# Pag2_Battery_Charger.net
KiCad netlist of a schematic drawn in Altium Designer
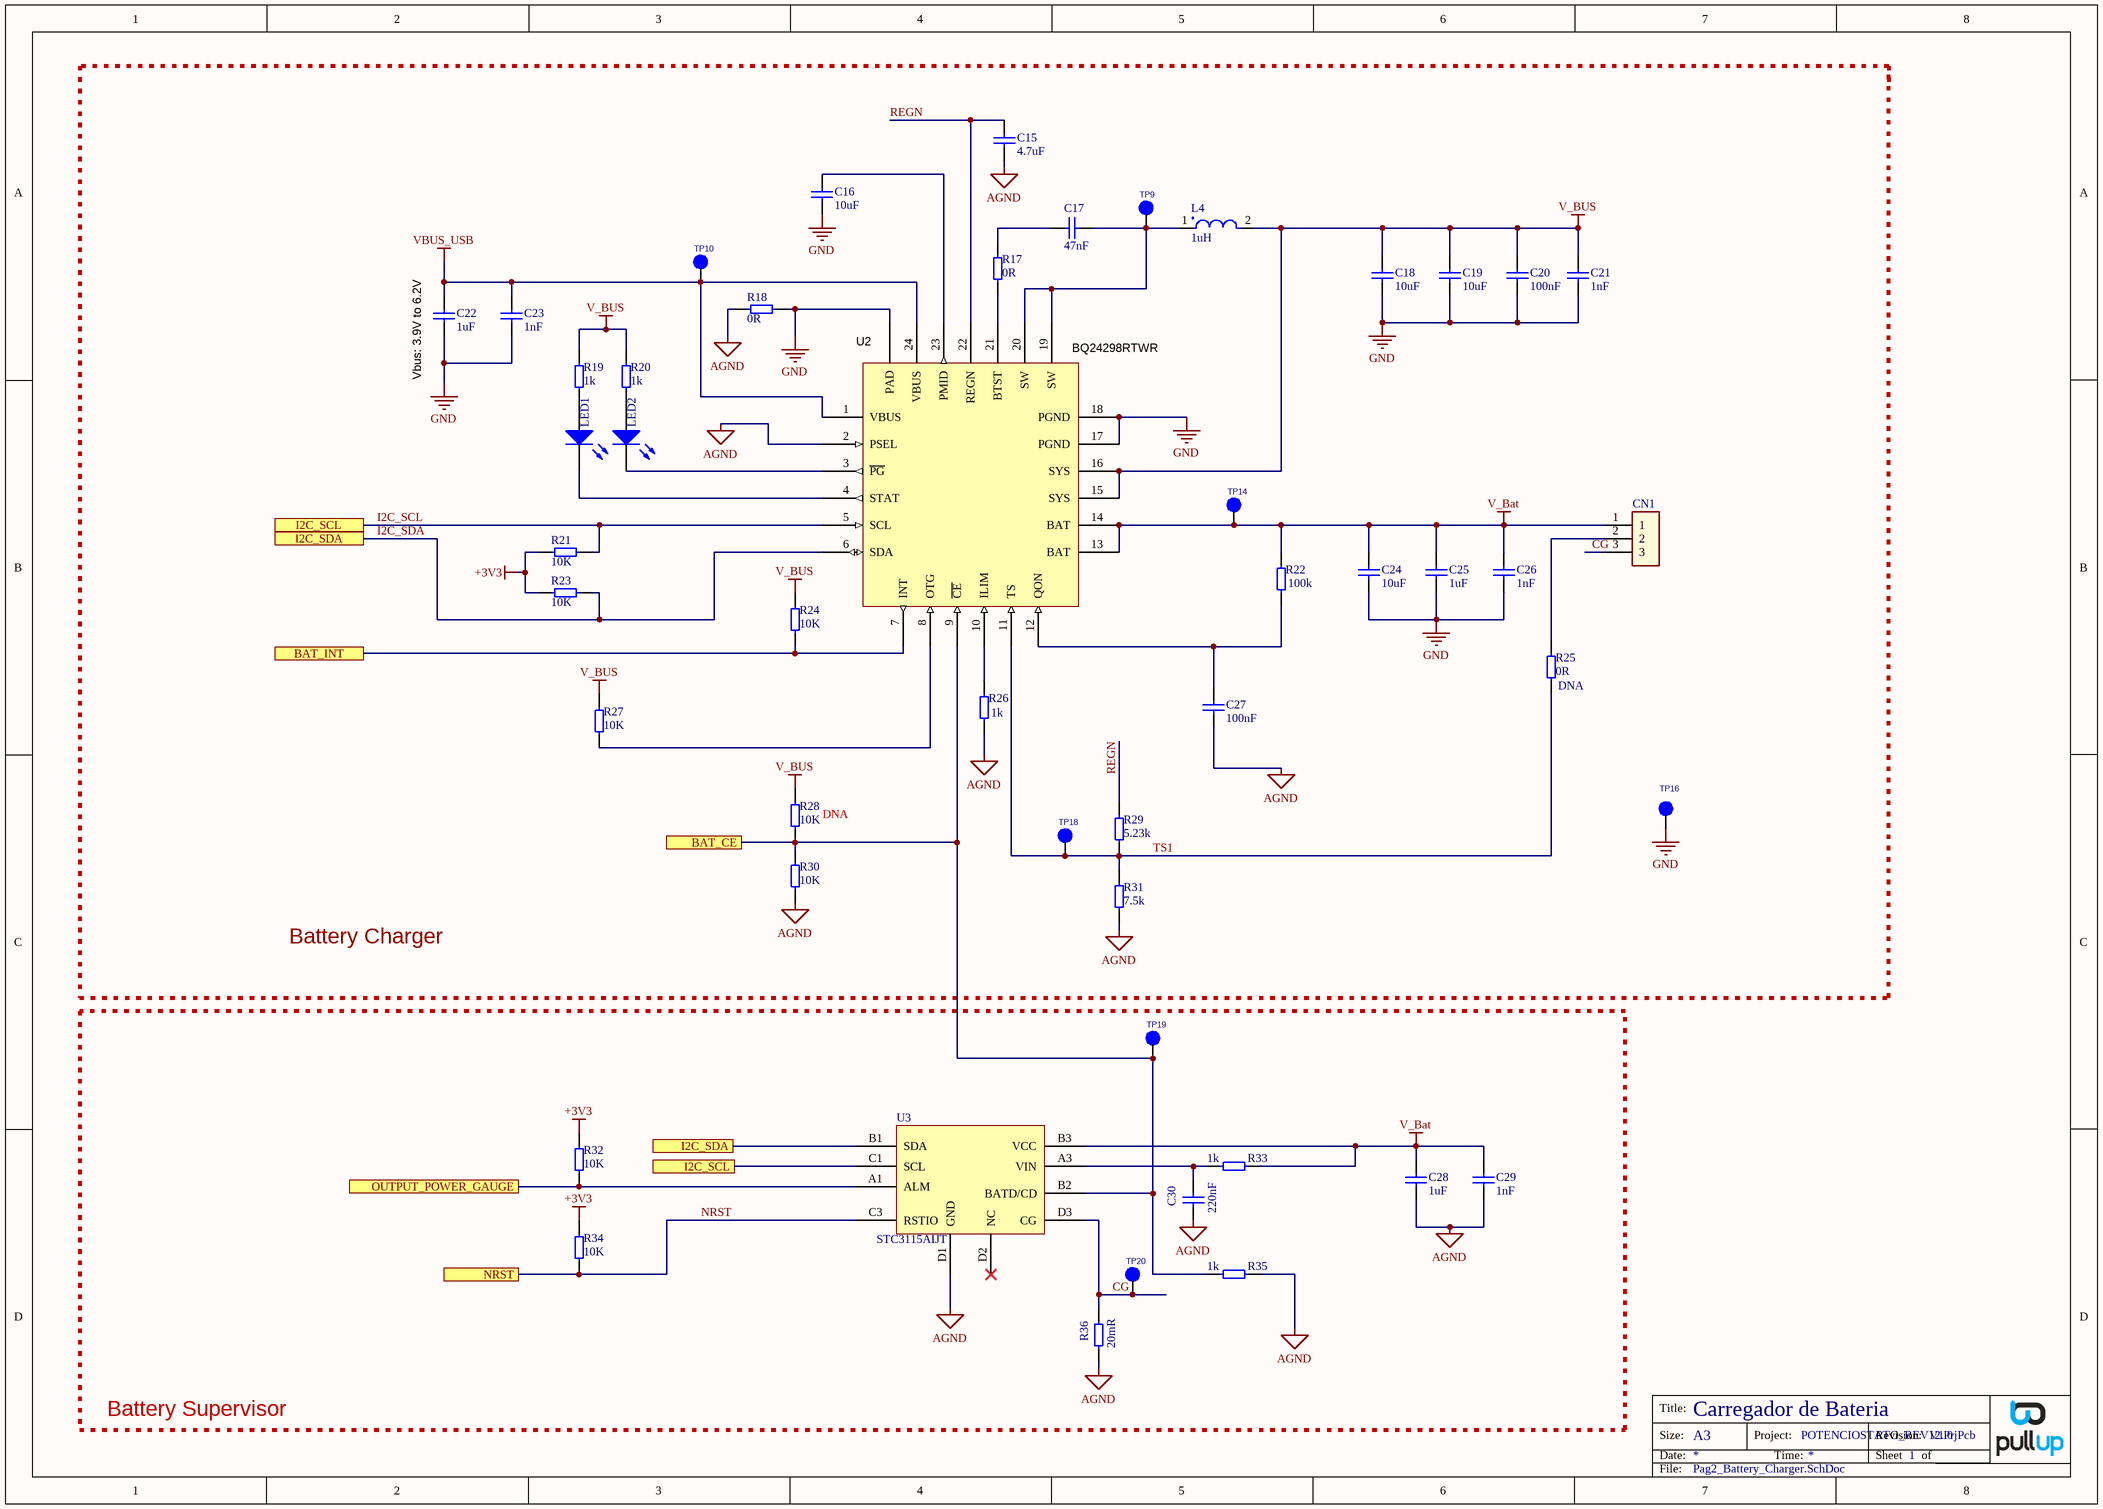
[diagram p0: Pag2_Battery_Charger.SchDoc]

(export (version "E")
  (design (tool "Eeschema 10.0.6"))
  (components
    (comp (ref "C15")
      (value "4.7uF")
      (footprint "0603")
      (description "Multilayer Ceramic Capacitors MLCC - SMD/SMT 4.7uF 6.3V 0603 10%")
      (fields (field (name "MANUFACTURER") "Taiyo Yuden") (field (name "MPN") "JMK105BBJ475MV-F"))
      (libsource (lib "Database_Pullup") (part "Cap"))
    )
    (comp (ref "C16")
      (value "10uF")
      (footprint "0603")
      (description "Multilayer Ceramic Capacitors MLCC - SMD/SMT 10uF 0603 10V 10%")
      (fields (field (name "MANUFACTURER") "Murata Electronics") (field (name "MPN") "GRM188R61A106KE69D"))
      (libsource (lib "Database_Pullup") (part "Cap"))
    )
    (comp (ref "C17")
      (value "47nF")
      (footprint "0603")
      (description "Multilayer Ceramic Capacitors MLCC - SMD/SMT 47nF 0603 16V 10%")
      (fields (field (name "MANUFACTURER") "AVX") (field (name "MPN") "0603YC473KAT2A"))
      (libsource (lib "Database_Pullup") (part "Cap"))
    )
    (comp (ref "C18")
      (value "10uF")
      (footprint "0603")
      (description "Multilayer Ceramic Capacitors MLCC - SMD/SMT 10uF 0603 10V 10%")
      (fields (field (name "MANUFACTURER") "Murata Electronics") (field (name "MPN") "GRM188R61A106KE69D"))
      (libsource (lib "Database_Pullup") (part "Cap"))
    )
    (comp (ref "C19")
      (value "10uF")
      (footprint "0603")
      (description "Multilayer Ceramic Capacitors MLCC - SMD/SMT 10uF 0603 10V 10%")
      (fields (field (name "MANUFACTURER") "Murata Electronics") (field (name "MPN") "GRM188R61A106KE69D"))
      (libsource (lib "Database_Pullup") (part "Cap"))
    )
    (comp (ref "C20")
      (value "100nF")
      (footprint "0603")
      (description "Multilayer Ceramic Capacitors MLCC - SMD/SMT 100nF 16V 0603 10%")
      (fields (field (name "MANUFACTURER") "KEMET") (field (name "MPN") "C0603C104K4RACTU"))
      (libsource (lib "Database_Pullup") (part "Cap"))
    )
    (comp (ref "C21")
      (value "1nF")
      (footprint "0603")
      (description "Multilayer Ceramic Capacitors MLCC - SMD/SMT 25V 1nF 0603 25V 5%")
      (fields (field (name "MANUFACTURER") "Yageo") (field (name "MPN") "CC0603JRX7R8BB102"))
      (libsource (lib "Database_Pullup") (part "Cap"))
    )
    (comp (ref "C22")
      (value "1uF")
      (footprint "0603")
      (description "Multilayer Ceramic Capacitors MLCC - SMD/SMT 1uF 25V 0603 10%")
      (fields
        (field (name "MANUFACTURER") "Samsung Electro-Mechanics")
        (field (name "MPN") "CL10A105KA8NNNC")
      )
      (libsource (lib "Database_Pullup") (part "Cap"))
    )
    (comp (ref "C23")
      (value "1nF")
      (footprint "0603")
      (description "Multilayer Ceramic Capacitors MLCC - SMD/SMT 25V 1nF 0603 25V 5%")
      (fields (field (name "MANUFACTURER") "Yageo") (field (name "MPN") "CC0603JRX7R8BB102"))
      (libsource (lib "Database_Pullup") (part "Cap"))
    )
    (comp (ref "C24")
      (value "10uF")
      (footprint "0603")
      (description "Multilayer Ceramic Capacitors MLCC - SMD/SMT 10uF 0603 10V 10%")
      (fields (field (name "MANUFACTURER") "Murata Electronics") (field (name "MPN") "GRM188R61A106KE69D"))
      (libsource (lib "Database_Pullup") (part "Cap"))
    )
    (comp (ref "C25")
      (value "1uF")
      (footprint "0603")
      (description "Multilayer Ceramic Capacitors MLCC - SMD/SMT 1uF 25V 0603 10%")
      (fields
        (field (name "MANUFACTURER") "Samsung Electro-Mechanics")
        (field (name "MPN") "CL10A105KA8NNNC")
      )
      (libsource (lib "Database_Pullup") (part "Cap"))
    )
    (comp (ref "C26")
      (value "1nF")
      (footprint "0603")
      (description "Multilayer Ceramic Capacitors MLCC - SMD/SMT 25V 1nF 0603 25V 5%")
      (fields (field (name "MANUFACTURER") "Yageo") (field (name "MPN") "CC0603JRX7R8BB102"))
      (libsource (lib "Database_Pullup") (part "Cap"))
    )
    (comp (ref "C27")
      (value "100nF")
      (footprint "0603")
      (description "Multilayer Ceramic Capacitors MLCC - SMD/SMT 100nF 16V 0603 10%")
      (fields (field (name "MANUFACTURER") "KEMET") (field (name "MPN") "C0603C104K4RACTU"))
      (libsource (lib "Database_Pullup") (part "Cap"))
    )
    (comp (ref "C28")
      (value "1uF")
      (footprint "0603")
      (description "Multilayer Ceramic Capacitors MLCC - SMD/SMT 1uF 25V 0603 10%")
      (fields
        (field (name "MANUFACTURER") "Samsung Electro-Mechanics")
        (field (name "MPN") "CL10A105KA8NNNC")
      )
      (libsource (lib "Database_Pullup") (part "Cap"))
    )
    (comp (ref "C29")
      (value "1nF")
      (footprint "0603")
      (description "Multilayer Ceramic Capacitors MLCC - SMD/SMT 25V 1nF 0603 25V 5%")
      (fields (field (name "MANUFACTURER") "Yageo") (field (name "MPN") "CC0603JRX7R8BB102"))
      (libsource (lib "Database_Pullup") (part "Cap"))
    )
    (comp (ref "C30")
      (value "220nF")
      (footprint "0603")
      (description "Multilayer Ceramic Capacitors MLCC - SMD/SMT 220nF 0603 16V 10%")
      (fields (field (name "MANUFACTURER") "Yageo") (field (name "MPN") "CC0603KRX7R7BB224"))
      (libsource (lib "Database_Pullup") (part "Cap"))
    )
    (comp (ref "CN1")
      (value "~")
      (footprint "HDR1X3 Large")
      (fields (field (name "MPN") "Header"))
      (libsource (lib "LIBSCH_PULLUP") (part "53254-0370"))
    )
    (comp (ref "L4")
      (value "1uH")
      (footprint "SRP4012TA")
      (description "Power Inductors - SMD 1uH 20% SMD 4012 AEC-Q200")
      (fields (field (name "MANUFACTURER") "Bourns") (field (name "MPN") "SRP4012TA-1R0M"))
      (libsource (lib "Database_Pullup") (part "IND"))
    )
    (comp (ref "LED1")
      (value "LED Green")
      (footprint "0603 - led")
      (description "Standard LEDs - SMD Green, Water Clear 60mcd, 571nm")
      (fields (field (name "MPN") "APG1608CGKC/T") (field (name "MANUFACTURER") "Kingbright"))
      (libsource (lib "Database_Pullup") (part "LED"))
    )
    (comp (ref "LED2")
      (value "LED Green")
      (footprint "0603 - led")
      (description "Standard LEDs - SMD Green, Water Clear 60mcd, 571nm")
      (fields (field (name "MPN") "APG1608CGKC/T") (field (name "MANUFACTURER") "Kingbright"))
      (libsource (lib "Database_Pullup") (part "LED"))
    )
    (comp (ref "R17")
      (value "0R")
      (footprint "0603")
      (description "Thick Film Resistors - SMD 0 Ohms 100 mW 0603 5%")
      (fields (field (name "MPN") "RC0603JR-070RL") (field (name "MANUFACTURER") "Yageo"))
      (libsource (lib "") (part "Res_2"))
    )
    (comp (ref "R18")
      (value "0R")
      (footprint "1218")
      (description "Thick Film Resistors - SMD 1watt zero ohm 1218")
      (fields (field (name "MANUFACTURER") "Yageo") (field (name "MPN") "RCL12180000Z0EK"))
      (libsource (lib "") (part "Res_1"))
    )
    (comp (ref "R19")
      (value "1k")
      (footprint "0603")
      (description "Thick Film Resistors - SMD 1 kOhms 100 mW 0603 5%")
      (fields (field (name "MPN") "RC0603JR-071KL") (field (name "MANUFACTURER") "Yageo"))
      (libsource (lib "") (part "Res_2"))
    )
    (comp (ref "R20")
      (value "1k")
      (footprint "0603")
      (description "Thick Film Resistors - SMD 1 kOhms 100 mW 0603 5%")
      (fields (field (name "MPN") "RC0603JR-071KL") (field (name "MANUFACTURER") "Yageo"))
      (libsource (lib "") (part "Res_2"))
    )
    (comp (ref "R21")
      (value "10K")
      (footprint "0603")
      (description "Thick Film Resistors - SMD 10 kOhms 100-200 mW 0603 1%")
      (fields (field (name "MANUFACTURER") "Yageo") (field (name "MPN") "RC0603FR-1310KL"))
      (libsource (lib "Database_Pullup_New") (part "Res"))
    )
    (comp (ref "R22")
      (value "100k")
      (footprint "0603")
      (description "Thick Film Resistors - SMD 100 kOhms 0603 100mW 1%")
      (fields (field (name "MPN") "RC0603FR-07100KL") (field (name "MANUFACTURER") "Yageo"))
      (libsource (lib "Database_Pullup") (part "Res"))
    )
    (comp (ref "R23")
      (value "10K")
      (footprint "0603")
      (description "Thick Film Resistors - SMD 10 kOhms 100-200 mW 0603 1%")
      (fields (field (name "MANUFACTURER") "Yageo") (field (name "MPN") "RC0603FR-1310KL"))
      (libsource (lib "Database_Pullup_New") (part "Res"))
    )
    (comp (ref "R24")
      (value "10K")
      (footprint "0603")
      (description "Thick Film Resistors - SMD 10 kOhms 100-200 mW 0603 1%")
      (fields (field (name "MANUFACTURER") "Yageo") (field (name "MPN") "RC0603FR-1310KL"))
      (libsource (lib "") (part "Res_1"))
    )
    (comp (ref "R25")
      (value "0R")
      (footprint "0603")
      (description "Thick Film Resistors - SMD 0 Ohms 100 mW 0603 5%")
      (fields
        (field (name "MPN") "RC0603JR-070RL")
        (field (name "MANUFACTURER") "Yageo")
        (field (name "PCBA") "DNA")
      )
      (libsource (lib "Database_Pullup") (part "Res"))
    )
    (comp (ref "R26")
      (value "1k")
      (footprint "0603")
      (description "Thick Film Resistors - SMD 1 kOhms 100 mW 0603 5%")
      (fields (field (name "MPN") "RC0603JR-071KL") (field (name "MANUFACTURER") "Yageo"))
      (libsource (lib "") (part "Res_2"))
    )
    (comp (ref "R27")
      (value "10K")
      (footprint "0603")
      (description "Thick Film Resistors - SMD 10 kOhms 100-200 mW 0603 1%")
      (fields (field (name "MANUFACTURER") "Yageo") (field (name "MPN") "RC0603FR-1310KL"))
      (libsource (lib "") (part "Res_1"))
    )
    (comp (ref "R28")
      (value "10K")
      (footprint "0603")
      (description "Thick Film Resistors - SMD 10 kOhms 100-200 mW 0603 1%")
      (fields
        (field (name "MANUFACTURER") "Yageo")
        (field (name "MPN") "RC0603FR-1310KL")
        (field (name "PCBA") "DNA")
      )
      (libsource (lib "") (part "Res_1"))
    )
    (comp (ref "R29")
      (value "5.23k")
      (footprint "0603")
      (description "Thick Film Resistors - SMD 5.23 kOhms 100mW 0603 1%")
      (fields (field (name "MANUFACTURER") "KOA") (field (name "MPN") "RK73H1JTTD5231F"))
      (libsource (lib "") (part "Res_2"))
    )
    (comp (ref "R30")
      (value "10K")
      (footprint "0603")
      (description "Thick Film Resistors - SMD 10 kOhms 100-200 mW 0603 1%")
      (fields (field (name "MANUFACTURER") "Yageo") (field (name "MPN") "RC0603FR-1310KL"))
      (libsource (lib "") (part "Res_1"))
    )
    (comp (ref "R31")
      (value "7.5k")
      (footprint "0603")
      (description "Thick Film Resistors - SMD 7.5 kOhms 100mW 0603 0.1%")
      (fields (field (name "MANUFACTURER") "KOA Speer") (field (name "MPN") "RN73R1JTTD7501B25"))
      (libsource (lib "") (part "Res_2"))
    )
    (comp (ref "R32")
      (value "10K")
      (footprint "0603")
      (description "Thick Film Resistors - SMD 10 kOhms 100-200 mW 0603 1%")
      (fields (field (name "MANUFACTURER") "Yageo") (field (name "MPN") "RC0603FR-1310KL"))
      (libsource (lib "") (part "Res_1"))
    )
    (comp (ref "R33")
      (value "1k")
      (footprint "0603")
      (description "Thick Film Resistors - SMD 1 kOhms 100 mW 0603 5%")
      (fields (field (name "MPN") "RC0603JR-071KL") (field (name "MANUFACTURER") "Yageo"))
      (libsource (lib "Database_Pullup_New") (part "Res"))
    )
    (comp (ref "R34")
      (value "10K")
      (footprint "0603")
      (description "Thick Film Resistors - SMD 10 kOhms 100-200 mW 0603 1%")
      (fields (field (name "MANUFACTURER") "Yageo") (field (name "MPN") "RC0603FR-1310KL"))
      (libsource (lib "") (part "Res_1"))
    )
    (comp (ref "R35")
      (value "1k")
      (footprint "0603")
      (description "Thick Film Resistors - SMD 1 kOhms 100 mW 0603 5%")
      (fields (field (name "MPN") "RC0603JR-071KL") (field (name "MANUFACTURER") "Yageo"))
      (libsource (lib "Database_Pullup_New") (part "Res"))
    )
    (comp (ref "R36")
      (value "20mR")
      (footprint "0805")
      (description "Current Sense Resistors - SMD .20mOhm 1% 1/2W")
      (fields (field (name "MPN") "CFN0603-FX-R020ELF") (field (name "MANUFACTURER") "Bourns"))
      (libsource (lib "") (part "Res_1"))
    )
    (comp (ref "TP9")
      (value "Test_Point")
      (footprint "TEST")
      (fields (field (name "MANUFACTURER") "DNA"))
      (libsource (lib "Database_Pullup") (part "TestLoop"))
    )
    (comp (ref "TP10")
      (value "Test_Point")
      (footprint "TEST")
      (fields (field (name "MANUFACTURER") "DNA"))
      (libsource (lib "Database_Pullup") (part "TestLoop"))
    )
    (comp (ref "TP14")
      (value "Test_Point")
      (footprint "TEST")
      (fields (field (name "MANUFACTURER") "DNA"))
      (libsource (lib "Database_Pullup") (part "TestLoop"))
    )
    (comp (ref "TP16")
      (value "Test_Point")
      (footprint "TEST")
      (fields (field (name "MANUFACTURER") "DNA"))
      (libsource (lib "Database_Pullup") (part "TestLoop"))
    )
    (comp (ref "TP18")
      (value "Test_Point")
      (footprint "TEST")
      (fields (field (name "MANUFACTURER") "DNA"))
      (libsource (lib "Database_Pullup") (part "TestLoop"))
    )
    (comp (ref "TP19")
      (value "Test_Point")
      (footprint "TEST")
      (fields (field (name "MANUFACTURER") "DNA"))
      (libsource (lib "Database_Pullup") (part "TestLoop"))
    )
    (comp (ref "TP20")
      (value "Test_Point")
      (footprint "TEST")
      (fields (field (name "MANUFACTURER") "DNA"))
      (libsource (lib "Database_Pullup") (part "TestLoop"))
    )
    (comp (ref "U2")
      (value "BQ24298RTWR")
      (footprint "WQFN-24")
      (fields (field (name "MANUFACTURER") "Texas Instruments"))
      (libsource (lib "Database_Pullup") (part "BQ24298RTWT"))
    )
    (comp (ref "U3")
      (value "STC3115AIJT")
      (footprint "CSP1.4X2.04")
      (description "Battery Management CONDITIONING & INTERFACES")
      (fields (field (name "MANUFACTURER") "STMicroelectronics"))
      (libsource (lib "LIBSCH_PULLUP") (part "STC3100"))
    )
  )
  (nets
    (net (code "1") (name "+3V3") (class "Default")
      (node (ref "R21") (pin "2") (pinfunction "2_2") (pintype "passive"))
      (node (ref "R23") (pin "2") (pinfunction "2_2") (pintype "passive"))
      (node (ref "R32") (pin "1") (pinfunction "1_1") (pintype "passive"))
      (node (ref "R34") (pin "1") (pinfunction "1_1") (pintype "passive"))
    )
    (net (code "2") (name "/BAT_CE") (class "Default")
      (node (ref "R28") (pin "2") (pinfunction "2_2") (pintype "passive"))
      (node (ref "R30") (pin "1") (pinfunction "1_1") (pintype "passive"))
      (node (ref "R35") (pin "2") (pinfunction "2_2") (pintype "passive"))
      (node (ref "TP19") (pin "1") (pinfunction "Pin1_1") (pintype "passive"))
      (node (ref "U2") (pin "9") (pinfunction "CE_9") (pintype "input"))
      (node (ref "U3") (pin "B2") (pinfunction "BATD/CD_B2") (pintype "passive"))
    )
    (net (code "3") (name "/BAT_INT") (class "Default")
      (node (ref "R24") (pin "2") (pinfunction "2_2") (pintype "passive"))
      (node (ref "U2") (pin "7") (pinfunction "INT_7") (pintype "output"))
    )
    (net (code "4") (name "/CG") (class "Default")
      (node (ref "CN1") (pin "3") (pinfunction "3_3") (pintype "passive"))
      (node (ref "R36") (pin "1") (pinfunction "1_1") (pintype "passive"))
      (node (ref "TP20") (pin "1") (pinfunction "Pin1_1") (pintype "passive"))
      (node (ref "U3") (pin "D3") (pinfunction "CG_D3") (pintype "passive"))
    )
    (net (code "5") (name "/I2C_SCL") (class "Default")
      (node (ref "R21") (pin "1") (pinfunction "1_1") (pintype "passive"))
      (node (ref "U2") (pin "5") (pinfunction "SCL_5") (pintype "input"))
      (node (ref "U3") (pin "C1") (pinfunction "SCL_C1") (pintype "passive"))
    )
    (net (code "6") (name "/I2C_SDA") (class "Default")
      (node (ref "R23") (pin "1") (pinfunction "1_1") (pintype "passive"))
      (node (ref "U2") (pin "6") (pinfunction "SDA_6") (pintype "bidirectional"))
      (node (ref "U3") (pin "B1") (pinfunction "SDA_B1") (pintype "passive"))
    )
    (net (code "7") (name "/NRST") (class "Default")
      (node (ref "R34") (pin "2") (pinfunction "2_2") (pintype "passive"))
      (node (ref "U3") (pin "C3") (pinfunction "RSTIO_C3") (pintype "passive"))
    )
    (net (code "8") (name "/OUTPUT_POWER_GAUGE") (class "Default")
      (node (ref "R32") (pin "2") (pinfunction "2_2") (pintype "passive"))
      (node (ref "U3") (pin "A1") (pinfunction "ALM_A1") (pintype "passive"))
    )
    (net (code "9") (name "/REGN") (class "Default")
      (node (ref "C15") (pin "2") (pinfunction "2_2") (pintype "passive"))
      (node (ref "R29") (pin "2") (pinfunction "2_2") (pintype "passive"))
      (node (ref "U2") (pin "22") (pinfunction "REGN_22") (pintype "power_in"))
    )
    (net (code "10") (name "/TS1") (class "Default")
      (node (ref "R25") (pin "2") (pinfunction "2_2") (pintype "passive"))
      (node (ref "R29") (pin "1") (pinfunction "1_1") (pintype "passive"))
      (node (ref "R31") (pin "2") (pinfunction "2_2") (pintype "passive"))
      (node (ref "TP18") (pin "1") (pinfunction "Pin1_1") (pintype "passive"))
      (node (ref "U2") (pin "11") (pinfunction "TS_11") (pintype "input"))
    )
    (net (code "11") (name "AGND") (class "Default")
      (node (ref "C15") (pin "1") (pinfunction "1_1") (pintype "passive"))
      (node (ref "C27") (pin "1") (pinfunction "1_1") (pintype "passive"))
      (node (ref "C28") (pin "1") (pinfunction "1_1") (pintype "passive"))
      (node (ref "C29") (pin "1") (pinfunction "1_1") (pintype "passive"))
      (node (ref "C30") (pin "1") (pinfunction "1_1") (pintype "passive"))
      (node (ref "R18") (pin "1") (pinfunction "1_1") (pintype "passive"))
      (node (ref "R26") (pin "1") (pinfunction "1_1") (pintype "passive"))
      (node (ref "R30") (pin "2") (pinfunction "2_2") (pintype "passive"))
      (node (ref "R31") (pin "1") (pinfunction "1_1") (pintype "passive"))
      (node (ref "R35") (pin "1") (pinfunction "1_1") (pintype "passive"))
      (node (ref "R36") (pin "2") (pinfunction "2_2") (pintype "passive"))
      (node (ref "U2") (pin "2") (pinfunction "PSEL_2") (pintype "input"))
      (node (ref "U3") (pin "D1") (pinfunction "GND_D1") (pintype "passive"))
    )
    (net (code "12") (name "GND") (class "Default")
      (node (ref "C16") (pin "1") (pinfunction "1_1") (pintype "passive"))
      (node (ref "C18") (pin "1") (pinfunction "1_1") (pintype "passive"))
      (node (ref "C19") (pin "1") (pinfunction "1_1") (pintype "passive"))
      (node (ref "C20") (pin "1") (pinfunction "1_1") (pintype "passive"))
      (node (ref "C21") (pin "1") (pinfunction "1_1") (pintype "passive"))
      (node (ref "C22") (pin "1") (pinfunction "1_1") (pintype "passive"))
      (node (ref "C23") (pin "1") (pinfunction "1_1") (pintype "passive"))
      (node (ref "C24") (pin "1") (pinfunction "1_1") (pintype "passive"))
      (node (ref "C25") (pin "1") (pinfunction "1_1") (pintype "passive"))
      (node (ref "C26") (pin "1") (pinfunction "1_1") (pintype "passive"))
      (node (ref "R18") (pin "2") (pinfunction "2_2") (pintype "passive"))
      (node (ref "TP16") (pin "1") (pinfunction "Pin1_1") (pintype "passive"))
      (node (ref "U2") (pin "17") (pinfunction "PGND_17") (pintype "power_in"))
      (node (ref "U2") (pin "18") (pinfunction "PGND_18") (pintype "power_in"))
      (node (ref "U2") (pin "25") (pinfunction "PAD_25") (pintype "power_in"))
    )
    (net (code "13") (name "Net-(C17-Pad2)") (class "Default")
      (node (ref "C17") (pin "2") (pinfunction "2_2") (pintype "passive"))
      (node (ref "R17") (pin "2") (pinfunction "2_2") (pintype "passive"))
    )
    (net (code "14") (name "Net-(CN1-Pad2)") (class "Default")
      (node (ref "CN1") (pin "2") (pinfunction "2_2") (pintype "passive"))
      (node (ref "R25") (pin "1") (pinfunction "1_1") (pintype "passive"))
    )
    (net (code "15") (name "Net-(LED1-A)") (class "Default")
      (node (ref "LED1") (pin "1") (pinfunction "A_1") (pintype "passive"))
      (node (ref "R19") (pin "1") (pinfunction "1_1") (pintype "passive"))
    )
    (net (code "16") (name "Net-(LED1-K)") (class "Default")
      (node (ref "LED1") (pin "2") (pinfunction "K_2") (pintype "passive"))
      (node (ref "U2") (pin "4") (pinfunction "STAT_4") (pintype "output"))
    )
    (net (code "17") (name "Net-(LED2-A)") (class "Default")
      (node (ref "LED2") (pin "1") (pinfunction "A_1") (pintype "passive"))
      (node (ref "R20") (pin "1") (pinfunction "1_1") (pintype "passive"))
    )
    (net (code "18") (name "Net-(LED2-K)") (class "Default")
      (node (ref "LED2") (pin "2") (pinfunction "K_2") (pintype "passive"))
      (node (ref "U2") (pin "3") (pinfunction "PG_3") (pintype "output"))
    )
    (net (code "19") (name "Net-(TP9-Pin1)") (class "Default")
      (node (ref "C17") (pin "1") (pinfunction "1_1") (pintype "passive"))
      (node (ref "L4") (pin "1") (pinfunction "1_1") (pintype "passive"))
      (node (ref "TP9") (pin "1") (pinfunction "Pin1_1") (pintype "passive"))
      (node (ref "U2") (pin "19") (pinfunction "SW_19") (pintype "power_in"))
      (node (ref "U2") (pin "20") (pinfunction "SW_20") (pintype "power_in"))
    )
    (net (code "20") (name "Net-(U2-BTST)") (class "Default")
      (node (ref "R17") (pin "1") (pinfunction "1_1") (pintype "passive"))
      (node (ref "U2") (pin "21") (pinfunction "BTST_21") (pintype "power_in"))
    )
    (net (code "21") (name "Net-(U2-ILIM)") (class "Default")
      (node (ref "R26") (pin "2") (pinfunction "2_2") (pintype "passive"))
      (node (ref "U2") (pin "10") (pinfunction "ILIM_10") (pintype "input"))
    )
    (net (code "22") (name "Net-(U2-OTG)") (class "Default")
      (node (ref "R27") (pin "2") (pinfunction "2_2") (pintype "passive"))
      (node (ref "U2") (pin "8") (pinfunction "OTG_8") (pintype "input"))
    )
    (net (code "23") (name "Net-(U2-PMID)") (class "Default")
      (node (ref "C16") (pin "2") (pinfunction "2_2") (pintype "passive"))
      (node (ref "U2") (pin "23") (pinfunction "PMID_23") (pintype "output"))
    )
    (net (code "24") (name "Net-(U2-QON)") (class "Default")
      (node (ref "C27") (pin "2") (pinfunction "2_2") (pintype "passive"))
      (node (ref "R22") (pin "2") (pinfunction "2_2") (pintype "passive"))
      (node (ref "U2") (pin "12") (pinfunction "QON_12") (pintype "input"))
    )
    (net (code "25") (name "Net-(U3-VIN)") (class "Default")
      (node (ref "C30") (pin "2") (pinfunction "2_2") (pintype "passive"))
      (node (ref "R33") (pin "2") (pinfunction "2_2") (pintype "passive"))
      (node (ref "U3") (pin "A3") (pinfunction "VIN_A3") (pintype "passive"))
    )
    (net (code "26") (name "VBUS_USB") (class "Default")
      (node (ref "C22") (pin "2") (pinfunction "2_2") (pintype "passive"))
      (node (ref "C23") (pin "2") (pinfunction "2_2") (pintype "passive"))
      (node (ref "TP10") (pin "1") (pinfunction "Pin1_1") (pintype "passive"))
      (node (ref "U2") (pin "1") (pinfunction "VBUS_1") (pintype "power_in"))
      (node (ref "U2") (pin "24") (pinfunction "VBUS_24") (pintype "power_in"))
    )
    (net (code "27") (name "V_BUS") (class "Default")
      (node (ref "C18") (pin "2") (pinfunction "2_2") (pintype "passive"))
      (node (ref "C19") (pin "2") (pinfunction "2_2") (pintype "passive"))
      (node (ref "C20") (pin "2") (pinfunction "2_2") (pintype "passive"))
      (node (ref "C21") (pin "2") (pinfunction "2_2") (pintype "passive"))
      (node (ref "L4") (pin "2") (pinfunction "2_2") (pintype "passive"))
      (node (ref "R19") (pin "2") (pinfunction "2_2") (pintype "passive"))
      (node (ref "R20") (pin "2") (pinfunction "2_2") (pintype "passive"))
      (node (ref "R24") (pin "1") (pinfunction "1_1") (pintype "passive"))
      (node (ref "R27") (pin "1") (pinfunction "1_1") (pintype "passive"))
      (node (ref "R28") (pin "1") (pinfunction "1_1") (pintype "passive"))
      (node (ref "U2") (pin "15") (pinfunction "SYS_15") (pintype "power_in"))
      (node (ref "U2") (pin "16") (pinfunction "SYS_16") (pintype "power_in"))
    )
    (net (code "28") (name "V_Bat") (class "Default")
      (node (ref "C24") (pin "2") (pinfunction "2_2") (pintype "passive"))
      (node (ref "C25") (pin "2") (pinfunction "2_2") (pintype "passive"))
      (node (ref "C26") (pin "2") (pinfunction "2_2") (pintype "passive"))
      (node (ref "C28") (pin "2") (pinfunction "2_2") (pintype "passive"))
      (node (ref "C29") (pin "2") (pinfunction "2_2") (pintype "passive"))
      (node (ref "CN1") (pin "1") (pinfunction "1_1") (pintype "passive"))
      (node (ref "R22") (pin "1") (pinfunction "1_1") (pintype "passive"))
      (node (ref "R33") (pin "1") (pinfunction "1_1") (pintype "passive"))
      (node (ref "TP14") (pin "1") (pinfunction "Pin1_1") (pintype "passive"))
      (node (ref "U2") (pin "13") (pinfunction "BAT_13") (pintype "power_in"))
      (node (ref "U2") (pin "14") (pinfunction "BAT_14") (pintype "power_in"))
      (node (ref "U3") (pin "B3") (pinfunction "VCC_B3") (pintype "passive"))
    )
    (net (code "29") (name "unconnected-(U3-NC-PadD2)") (class "Default")
      (node (ref "U3") (pin "D2") (pinfunction "NC_D2") (pintype "passive+no_connect"))
    )
  )
)
